# MODULE_SAIL.net
KiCad netlist of a schematic drawn in Altium Designer
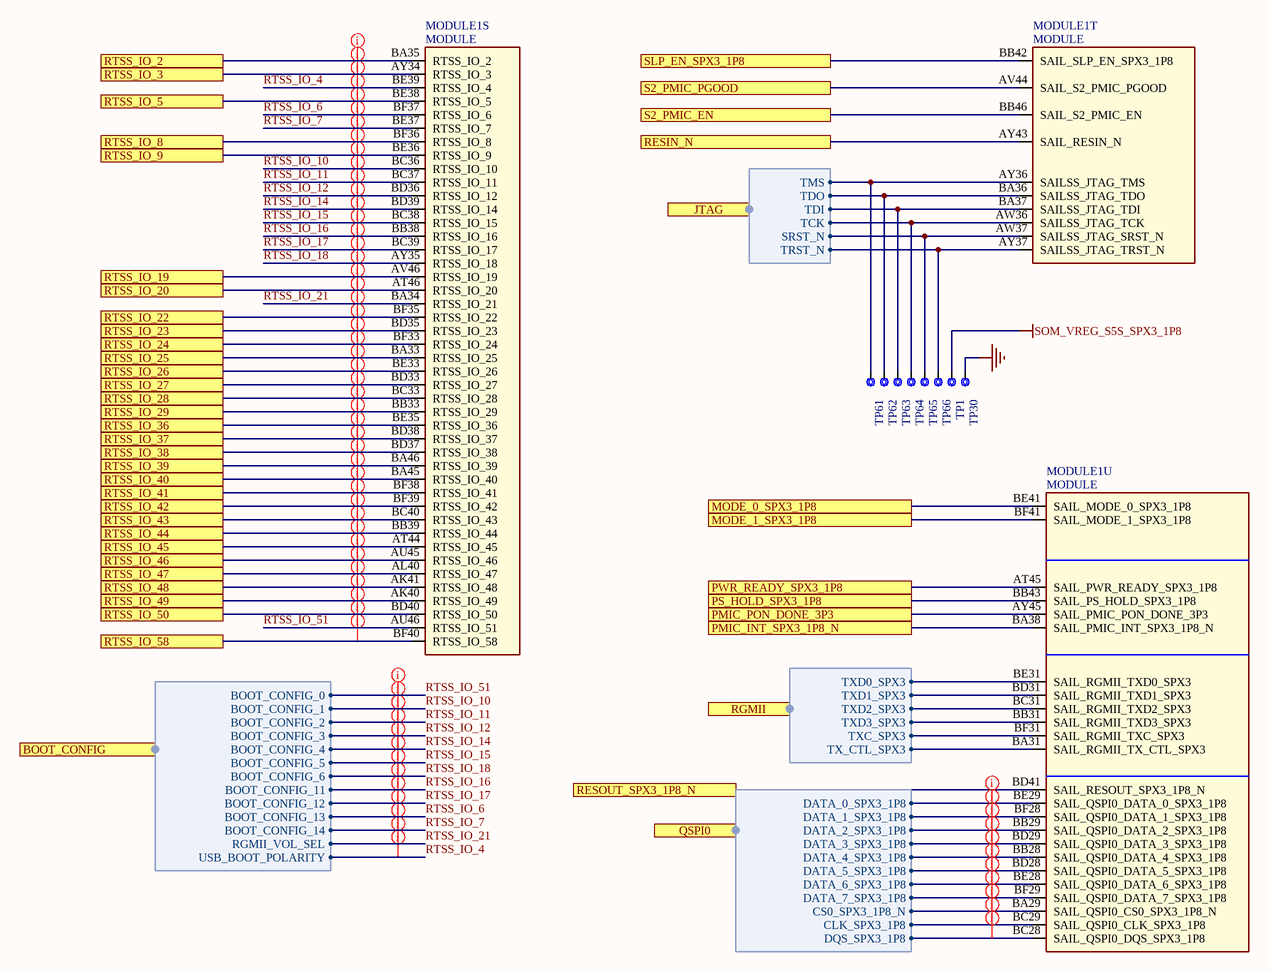
[diagram p0: MODULE_SAIL.SchDoc]

(export (version "E")
  (design (tool "Eeschema 10.0.6"))
  (components
    (comp (ref "MODULE1")
      (value "MODULE")
      (footprint "MODULE")
      (description "MODULE BGA 1883 balls 57.5x57.5mm")
      (fields (field (name "MANUFACTURER") "Qualcomm") (field (name "PART NUMBER") "MODULE BGA"))
      (libsource (lib "Clean") (part "MODULE"))
    )
    (comp (ref "TP1")
      (value "Test point 1.00mm")
      (footprint "TP-1.00MM")
      (fields (field (name "PART NUMBER") "This is not a component"))
      (libsource (lib "Clean") (part "TESTPOINT"))
    )
    (comp (ref "TP30")
      (value "Test point 1.00mm")
      (footprint "TP-1.00MM")
      (fields (field (name "PART NUMBER") "This is not a component"))
      (libsource (lib "Clean") (part "TESTPOINT"))
    )
    (comp (ref "TP61")
      (value "Test point 1.00mm")
      (footprint "TP-1.00MM")
      (fields (field (name "PART NUMBER") "This is not a component"))
      (libsource (lib "Clean") (part "TESTPOINT"))
    )
    (comp (ref "TP62")
      (value "Test point 1.00mm")
      (footprint "TP-1.00MM")
      (fields (field (name "PART NUMBER") "This is not a component"))
      (libsource (lib "Clean") (part "TESTPOINT"))
    )
    (comp (ref "TP63")
      (value "Test point 1.00mm")
      (footprint "TP-1.00MM")
      (fields (field (name "PART NUMBER") "This is not a component"))
      (libsource (lib "Clean") (part "TESTPOINT"))
    )
    (comp (ref "TP64")
      (value "Test point 1.00mm")
      (footprint "TP-1.00MM")
      (fields (field (name "PART NUMBER") "This is not a component"))
      (libsource (lib "Clean") (part "TESTPOINT"))
    )
    (comp (ref "TP65")
      (value "Test point 1.00mm")
      (footprint "TP-1.00MM")
      (fields (field (name "PART NUMBER") "This is not a component"))
      (libsource (lib "Clean") (part "TESTPOINT"))
    )
    (comp (ref "TP66")
      (value "Test point 1.00mm")
      (footprint "TP-1.00MM")
      (fields (field (name "PART NUMBER") "This is not a component"))
      (libsource (lib "Clean") (part "TESTPOINT"))
    )
  )
  (nets
    (net (code "5") (name "/CLK_SPX3_1P8") (class "Default")
      (node (ref "MODULE1") (pin "BC29") (pinfunction "SAIL_QSPI0_CLK_SPX3_1P8_BC29") (pintype "passive"))
    )
    (net (code "6") (name "/CS0_SPX3_1P8_N") (class "Default")
      (node (ref "MODULE1") (pin "BA29") (pinfunction "SAIL_QSPI0_CS0_SPX3_1P8_N_BA29") (pintype "passive"))
    )
    (net (code "7") (name "/DATA_0_SPX3_1P8") (class "Default")
      (node (ref "MODULE1") (pin "BE29") (pinfunction "SAIL_QSPI0_DATA_0_SPX3_1P8_BE29") (pintype "passive"))
    )
    (net (code "8") (name "/DATA_1_SPX3_1P8") (class "Default")
      (node (ref "MODULE1") (pin "BF28") (pinfunction "SAIL_QSPI0_DATA_1_SPX3_1P8_BF28") (pintype "passive"))
    )
    (net (code "9") (name "/DATA_2_SPX3_1P8") (class "Default")
      (node (ref "MODULE1") (pin "BB29") (pinfunction "SAIL_QSPI0_DATA_2_SPX3_1P8_BB29") (pintype "passive"))
    )
    (net (code "10") (name "/DATA_3_SPX3_1P8") (class "Default")
      (node (ref "MODULE1") (pin "BD29") (pinfunction "SAIL_QSPI0_DATA_3_SPX3_1P8_BD29") (pintype "passive"))
    )
    (net (code "11") (name "/DATA_4_SPX3_1P8") (class "Default")
      (node (ref "MODULE1") (pin "BB28") (pinfunction "SAIL_QSPI0_DATA_4_SPX3_1P8_BB28") (pintype "passive"))
    )
    (net (code "12") (name "/DATA_5_SPX3_1P8") (class "Default")
      (node (ref "MODULE1") (pin "BD28") (pinfunction "SAIL_QSPI0_DATA_5_SPX3_1P8_BD28") (pintype "passive"))
    )
    (net (code "13") (name "/DATA_6_SPX3_1P8") (class "Default")
      (node (ref "MODULE1") (pin "BE28") (pinfunction "SAIL_QSPI0_DATA_6_SPX3_1P8_BE28") (pintype "passive"))
    )
    (net (code "14") (name "/DATA_7_SPX3_1P8") (class "Default")
      (node (ref "MODULE1") (pin "BF29") (pinfunction "SAIL_QSPI0_DATA_7_SPX3_1P8_BF29") (pintype "passive"))
    )
    (net (code "15") (name "/DQS_SPX3_1P8") (class "Default")
      (node (ref "MODULE1") (pin "BC28") (pinfunction "SAIL_QSPI0_DQS_SPX3_1P8_BC28") (pintype "passive"))
    )
    (net (code "16") (name "/MODE_0_SPX3_1P8") (class "Default")
      (node (ref "MODULE1") (pin "BE41") (pinfunction "SAIL_MODE_0_SPX3_1P8_BE41") (pintype "passive"))
    )
    (net (code "17") (name "/MODE_1_SPX3_1P8") (class "Default")
      (node (ref "MODULE1") (pin "BF41") (pinfunction "SAIL_MODE_1_SPX3_1P8_BF41") (pintype "passive"))
    )
    (net (code "18") (name "/PMIC_INT_SPX3_1P8_N") (class "Default")
      (node (ref "MODULE1") (pin "BA38") (pinfunction "SAIL_PMIC_INT_SPX3_1P8_N_BA38") (pintype "passive"))
    )
    (net (code "19") (name "/PMIC_PON_DONE_3P3") (class "Default")
      (node (ref "MODULE1") (pin "AY45") (pinfunction "SAIL_PMIC_PON_DONE_3P3_AY45") (pintype "passive"))
    )
    (net (code "20") (name "/PS_HOLD_SPX3_1P8") (class "Default")
      (node (ref "MODULE1") (pin "BB43") (pinfunction "SAIL_PS_HOLD_SPX3_1P8_BB43") (pintype "passive"))
    )
    (net (code "21") (name "/PWR_READY_SPX3_1P8") (class "Default")
      (node (ref "MODULE1") (pin "AT45") (pinfunction "SAIL_PWR_READY_SPX3_1P8_AT45") (pintype "passive"))
    )
    (net (code "22") (name "/RESIN_N") (class "Default")
      (node (ref "MODULE1") (pin "AY43") (pinfunction "SAIL_RESIN_N_AY43") (pintype "passive"))
    )
    (net (code "23") (name "/RESOUT_SPX3_1P8_N") (class "Default")
      (node (ref "MODULE1") (pin "BD41") (pinfunction "SAIL_RESOUT_SPX3_1P8_N_BD41") (pintype "passive"))
    )
    (net (code "24") (name "/RTSS_IO_2") (class "Default")
      (node (ref "MODULE1") (pin "BA35") (pinfunction "RTSS_IO_2_BA35") (pintype "passive"))
    )
    (net (code "25") (name "/RTSS_IO_3") (class "Default")
      (node (ref "MODULE1") (pin "AY34") (pinfunction "RTSS_IO_3_AY34") (pintype "passive"))
    )
    (net (code "26") (name "/RTSS_IO_4") (class "Default")
      (node (ref "MODULE1") (pin "BE39") (pinfunction "RTSS_IO_4_BE39") (pintype "passive"))
    )
    (net (code "27") (name "/RTSS_IO_5") (class "Default")
      (node (ref "MODULE1") (pin "BE38") (pinfunction "RTSS_IO_5_BE38") (pintype "passive"))
    )
    (net (code "28") (name "/RTSS_IO_6") (class "Default")
      (node (ref "MODULE1") (pin "BF37") (pinfunction "RTSS_IO_6_BF37") (pintype "passive"))
    )
    (net (code "29") (name "/RTSS_IO_7") (class "Default")
      (node (ref "MODULE1") (pin "BE37") (pinfunction "RTSS_IO_7_BE37") (pintype "passive"))
    )
    (net (code "30") (name "/RTSS_IO_8") (class "Default")
      (node (ref "MODULE1") (pin "BF36") (pinfunction "RTSS_IO_8_BF36") (pintype "passive"))
    )
    (net (code "31") (name "/RTSS_IO_9") (class "Default")
      (node (ref "MODULE1") (pin "BE36") (pinfunction "RTSS_IO_9_BE36") (pintype "passive"))
    )
    (net (code "32") (name "/RTSS_IO_10") (class "Default")
      (node (ref "MODULE1") (pin "BC36") (pinfunction "RTSS_IO_10_BC36") (pintype "passive"))
    )
    (net (code "33") (name "/RTSS_IO_11") (class "Default")
      (node (ref "MODULE1") (pin "BC37") (pinfunction "RTSS_IO_11_BC37") (pintype "passive"))
    )
    (net (code "34") (name "/RTSS_IO_12") (class "Default")
      (node (ref "MODULE1") (pin "BD36") (pinfunction "RTSS_IO_12_BD36") (pintype "passive"))
    )
    (net (code "35") (name "/RTSS_IO_14") (class "Default")
      (node (ref "MODULE1") (pin "BD39") (pinfunction "RTSS_IO_14_BD39") (pintype "passive"))
    )
    (net (code "36") (name "/RTSS_IO_15") (class "Default")
      (node (ref "MODULE1") (pin "BC38") (pinfunction "RTSS_IO_15_BC38") (pintype "passive"))
    )
    (net (code "37") (name "/RTSS_IO_16") (class "Default")
      (node (ref "MODULE1") (pin "BB38") (pinfunction "RTSS_IO_16_BB38") (pintype "passive"))
    )
    (net (code "38") (name "/RTSS_IO_17") (class "Default")
      (node (ref "MODULE1") (pin "BC39") (pinfunction "RTSS_IO_17_BC39") (pintype "passive"))
    )
    (net (code "39") (name "/RTSS_IO_18") (class "Default")
      (node (ref "MODULE1") (pin "AY35") (pinfunction "RTSS_IO_18_AY35") (pintype "passive"))
    )
    (net (code "40") (name "/RTSS_IO_19") (class "Default")
      (node (ref "MODULE1") (pin "AV46") (pinfunction "RTSS_IO_19_AV46") (pintype "passive"))
    )
    (net (code "41") (name "/RTSS_IO_20") (class "Default")
      (node (ref "MODULE1") (pin "AT46") (pinfunction "RTSS_IO_20_AT46") (pintype "passive"))
    )
    (net (code "42") (name "/RTSS_IO_21") (class "Default")
      (node (ref "MODULE1") (pin "BA34") (pinfunction "RTSS_IO_21_BA34") (pintype "passive"))
    )
    (net (code "43") (name "/RTSS_IO_22") (class "Default")
      (node (ref "MODULE1") (pin "BF35") (pinfunction "RTSS_IO_22_BF35") (pintype "passive"))
    )
    (net (code "44") (name "/RTSS_IO_23") (class "Default")
      (node (ref "MODULE1") (pin "BD35") (pinfunction "RTSS_IO_23_BD35") (pintype "passive"))
    )
    (net (code "45") (name "/RTSS_IO_24") (class "Default")
      (node (ref "MODULE1") (pin "BF33") (pinfunction "RTSS_IO_24_BF33") (pintype "passive"))
    )
    (net (code "46") (name "/RTSS_IO_25") (class "Default")
      (node (ref "MODULE1") (pin "BA33") (pinfunction "RTSS_IO_25_BA33") (pintype "passive"))
    )
    (net (code "47") (name "/RTSS_IO_26") (class "Default")
      (node (ref "MODULE1") (pin "BE33") (pinfunction "RTSS_IO_26_BE33") (pintype "passive"))
    )
    (net (code "48") (name "/RTSS_IO_27") (class "Default")
      (node (ref "MODULE1") (pin "BD33") (pinfunction "RTSS_IO_27_BD33") (pintype "passive"))
    )
    (net (code "49") (name "/RTSS_IO_28") (class "Default")
      (node (ref "MODULE1") (pin "BC33") (pinfunction "RTSS_IO_28_BC33") (pintype "passive"))
    )
    (net (code "50") (name "/RTSS_IO_29") (class "Default")
      (node (ref "MODULE1") (pin "BB33") (pinfunction "RTSS_IO_29_BB33") (pintype "passive"))
    )
    (net (code "51") (name "/RTSS_IO_36") (class "Default")
      (node (ref "MODULE1") (pin "BE35") (pinfunction "RTSS_IO_36_BE35") (pintype "passive"))
    )
    (net (code "52") (name "/RTSS_IO_37") (class "Default")
      (node (ref "MODULE1") (pin "BD38") (pinfunction "RTSS_IO_37_BD38") (pintype "passive"))
    )
    (net (code "53") (name "/RTSS_IO_38") (class "Default")
      (node (ref "MODULE1") (pin "BD37") (pinfunction "RTSS_IO_38_BD37") (pintype "passive"))
    )
    (net (code "54") (name "/RTSS_IO_39") (class "Default")
      (node (ref "MODULE1") (pin "BA46") (pinfunction "RTSS_IO_39_BA46") (pintype "passive"))
    )
    (net (code "55") (name "/RTSS_IO_40") (class "Default")
      (node (ref "MODULE1") (pin "BA45") (pinfunction "RTSS_IO_40_BA45") (pintype "passive"))
    )
    (net (code "56") (name "/RTSS_IO_41") (class "Default")
      (node (ref "MODULE1") (pin "BF38") (pinfunction "RTSS_IO_41_BF38") (pintype "passive"))
    )
    (net (code "57") (name "/RTSS_IO_42") (class "Default")
      (node (ref "MODULE1") (pin "BF39") (pinfunction "RTSS_IO_42_BF39") (pintype "passive"))
    )
    (net (code "58") (name "/RTSS_IO_43") (class "Default")
      (node (ref "MODULE1") (pin "BC40") (pinfunction "RTSS_IO_43_BC40") (pintype "passive"))
    )
    (net (code "59") (name "/RTSS_IO_44") (class "Default")
      (node (ref "MODULE1") (pin "BB39") (pinfunction "RTSS_IO_44_BB39") (pintype "passive"))
    )
    (net (code "60") (name "/RTSS_IO_45") (class "Default")
      (node (ref "MODULE1") (pin "AT44") (pinfunction "RTSS_IO_45_AT44") (pintype "passive"))
    )
    (net (code "61") (name "/RTSS_IO_46") (class "Default")
      (node (ref "MODULE1") (pin "AU45") (pinfunction "RTSS_IO_46_AU45") (pintype "passive"))
    )
    (net (code "62") (name "/RTSS_IO_47") (class "Default")
      (node (ref "MODULE1") (pin "AL40") (pinfunction "RTSS_IO_47_AL40") (pintype "passive"))
    )
    (net (code "63") (name "/RTSS_IO_48") (class "Default")
      (node (ref "MODULE1") (pin "AK41") (pinfunction "RTSS_IO_48_AK41") (pintype "passive"))
    )
    (net (code "64") (name "/RTSS_IO_49") (class "Default")
      (node (ref "MODULE1") (pin "AK40") (pinfunction "RTSS_IO_49_AK40") (pintype "passive"))
    )
    (net (code "65") (name "/RTSS_IO_50") (class "Default")
      (node (ref "MODULE1") (pin "BD40") (pinfunction "RTSS_IO_50_BD40") (pintype "passive"))
    )
    (net (code "66") (name "/RTSS_IO_51") (class "Default")
      (node (ref "MODULE1") (pin "AU46") (pinfunction "RTSS_IO_51_AU46") (pintype "passive"))
    )
    (net (code "67") (name "/RTSS_IO_58") (class "Default")
      (node (ref "MODULE1") (pin "BF40") (pinfunction "RTSS_IO_58_BF40") (pintype "passive"))
    )
    (net (code "68") (name "/S2_PMIC_EN") (class "Default")
      (node (ref "MODULE1") (pin "BB46") (pinfunction "SAIL_S2_PMIC_EN_BB46") (pintype "passive"))
    )
    (net (code "69") (name "/S2_PMIC_PGOOD") (class "Default")
      (node (ref "MODULE1") (pin "AV44") (pinfunction "SAIL_S2_PMIC_PGOOD_AV44") (pintype "passive"))
    )
    (net (code "70") (name "/SLP_EN_SPX3_1P8") (class "Default")
      (node (ref "MODULE1") (pin "BB42") (pinfunction "SAIL_SLP_EN_SPX3_1P8_BB42") (pintype "passive"))
    )
    (net (code "71") (name "/SRST_N") (class "Default")
      (node (ref "MODULE1") (pin "AW37") (pinfunction "SAILSS_JTAG_SRST_N_AW37") (pintype "passive"))
      (node (ref "TP65") (pin "X") (pinfunction "X_X") (pintype "passive"))
    )
    (net (code "72") (name "/TCK") (class "Default")
      (node (ref "MODULE1") (pin "AW36") (pinfunction "SAILSS_JTAG_TCK_AW36") (pintype "passive"))
      (node (ref "TP64") (pin "X") (pinfunction "X_X") (pintype "passive"))
    )
    (net (code "73") (name "/TDI") (class "Default")
      (node (ref "MODULE1") (pin "BA37") (pinfunction "SAILSS_JTAG_TDI_BA37") (pintype "passive"))
      (node (ref "TP63") (pin "X") (pinfunction "X_X") (pintype "passive"))
    )
    (net (code "74") (name "/TDO") (class "Default")
      (node (ref "MODULE1") (pin "BA36") (pinfunction "SAILSS_JTAG_TDO_BA36") (pintype "passive"))
      (node (ref "TP62") (pin "X") (pinfunction "X_X") (pintype "passive"))
    )
    (net (code "75") (name "/TMS") (class "Default")
      (node (ref "MODULE1") (pin "AY36") (pinfunction "SAILSS_JTAG_TMS_AY36") (pintype "passive"))
      (node (ref "TP61") (pin "X") (pinfunction "X_X") (pintype "passive"))
    )
    (net (code "76") (name "/TRST_N") (class "Default")
      (node (ref "MODULE1") (pin "AY37") (pinfunction "SAILSS_JTAG_TRST_N_AY37") (pintype "passive"))
      (node (ref "TP66") (pin "X") (pinfunction "X_X") (pintype "passive"))
    )
    (net (code "77") (name "/TXC_SPX3") (class "Default")
      (node (ref "MODULE1") (pin "BF31") (pinfunction "SAIL_RGMII_TXC_SPX3_BF31") (pintype "passive"))
    )
    (net (code "78") (name "/TXD0_SPX3") (class "Default")
      (node (ref "MODULE1") (pin "BE31") (pinfunction "SAIL_RGMII_TXD0_SPX3_BE31") (pintype "passive"))
    )
    (net (code "79") (name "/TXD1_SPX3") (class "Default")
      (node (ref "MODULE1") (pin "BD31") (pinfunction "SAIL_RGMII_TXD1_SPX3_BD31") (pintype "passive"))
    )
    (net (code "80") (name "/TXD2_SPX3") (class "Default")
      (node (ref "MODULE1") (pin "BC31") (pinfunction "SAIL_RGMII_TXD2_SPX3_BC31") (pintype "passive"))
    )
    (net (code "81") (name "/TXD3_SPX3") (class "Default")
      (node (ref "MODULE1") (pin "BB31") (pinfunction "SAIL_RGMII_TXD3_SPX3_BB31") (pintype "passive"))
    )
    (net (code "82") (name "/TX_CTL_SPX3") (class "Default")
      (node (ref "MODULE1") (pin "BA31") (pinfunction "SAIL_RGMII_TX_CTL_SPX3_BA31") (pintype "passive"))
    )
    (net (code "87") (name "GND") (class "Default")
      (node (ref "TP30") (pin "X") (pinfunction "X_X") (pintype "passive"))
    )
    (net (code "88") (name "SOM_VREG_S5S_SPX3_1P8") (class "Default")
      (node (ref "TP1") (pin "X") (pinfunction "X_X") (pintype "passive"))
    )
  )
)
